# D32_Pro_Breakout_-_TFT_Touch.net
KiCad netlist of a schematic drawn in EAGLE
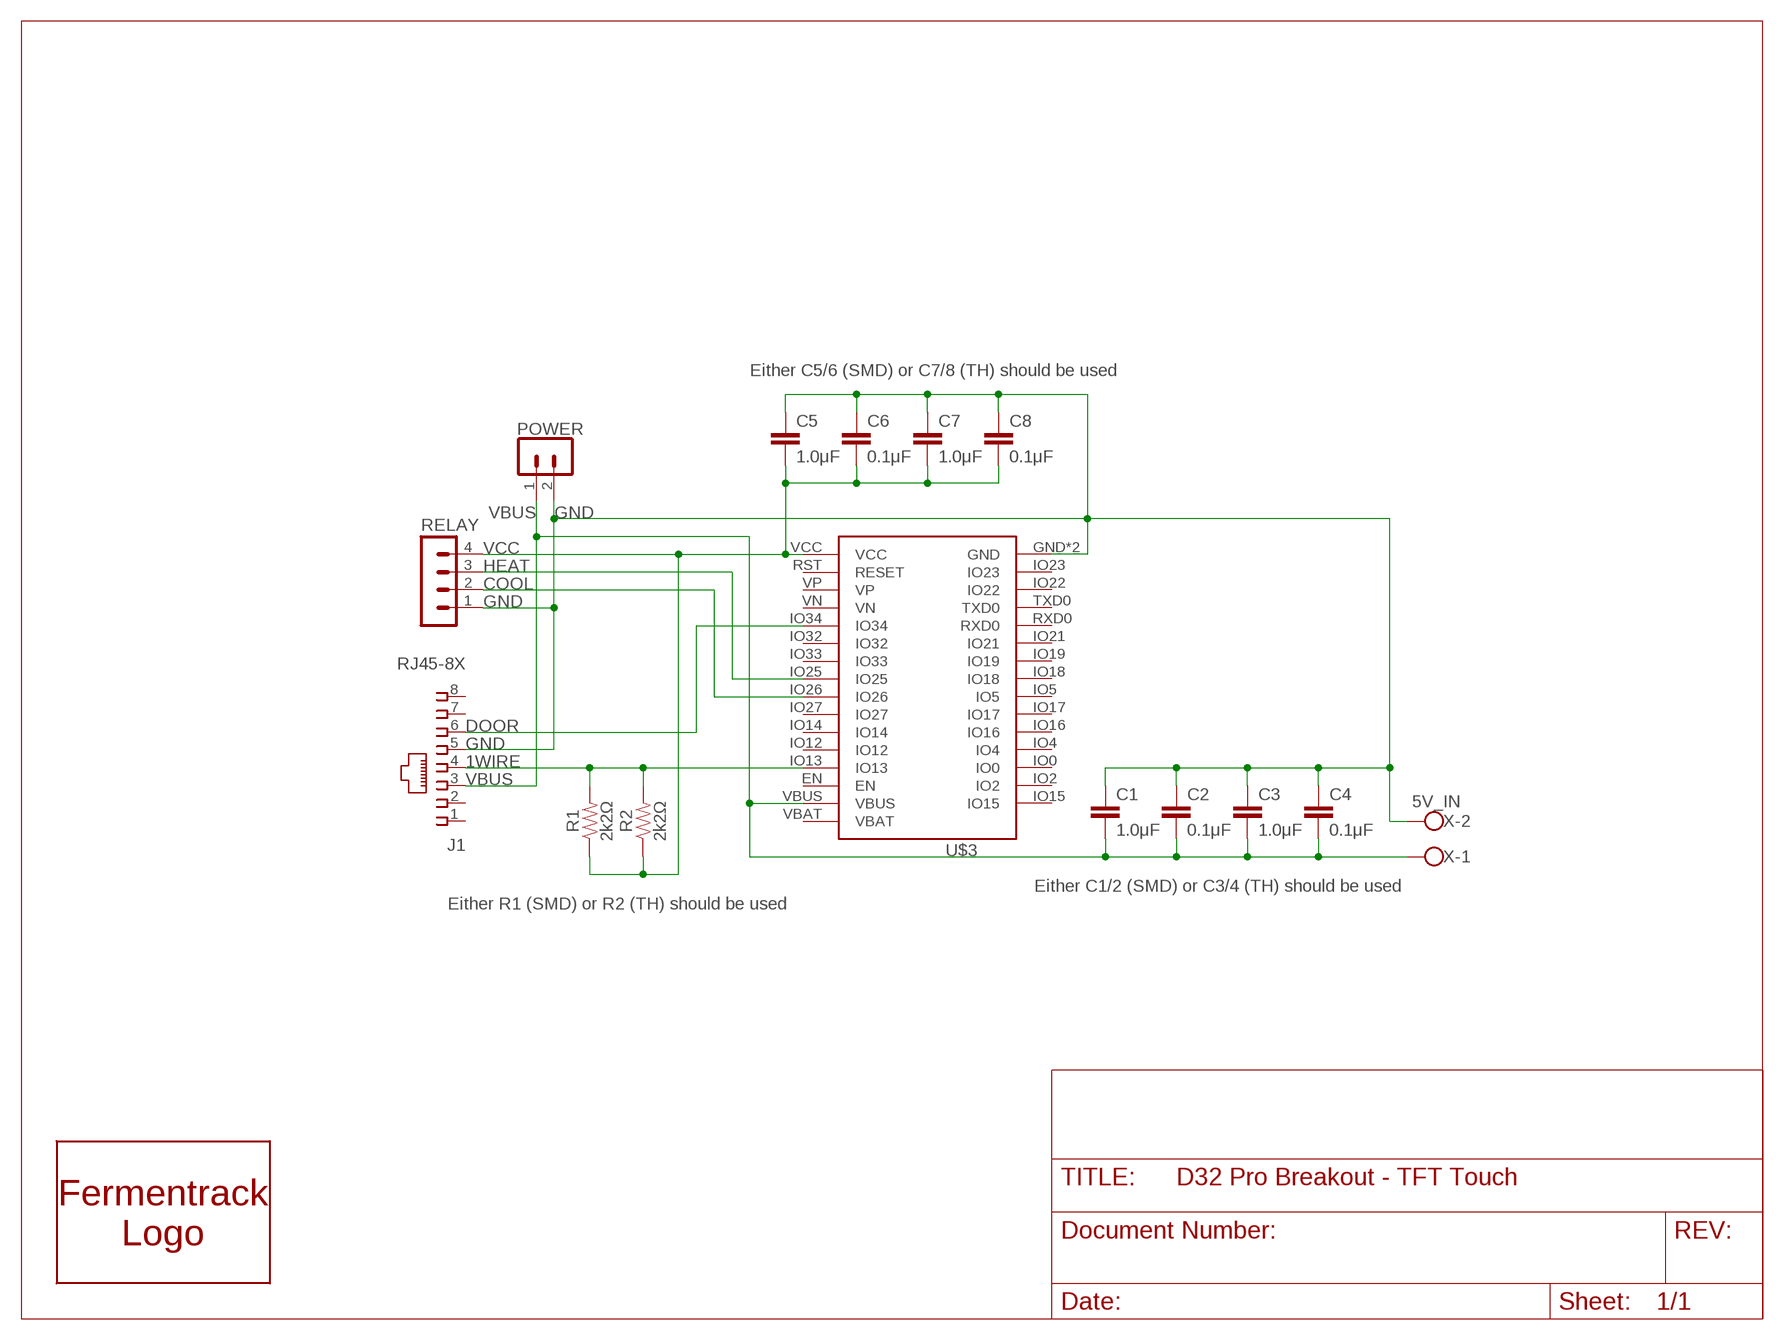
[diagram p0: schematic, sheet 1]

(export (version "E")
  (design (tool "Eeschema 10.0.6"))
  (components
    (comp (ref "C1")
      (value "1.0μF")
      (footprint "eagle-import:SMD-1206")
      (libsource (lib "eagle-import") (part "CAP_SMD1206"))
    )
    (comp (ref "C2")
      (value "0.1μF")
      (footprint "eagle-import:SMD-1206")
      (libsource (lib "eagle-import") (part "CAP_SMD1206"))
    )
    (comp (ref "C3")
      (value "1.0μF")
      (footprint "eagle-import:CAP_PTH-2.54")
      (libsource (lib "eagle-import") (part "CAP_CERAMIC_2.54"))
    )
    (comp (ref "C4")
      (value "0.1μF")
      (footprint "eagle-import:CAP_PTH-2.54")
      (libsource (lib "eagle-import") (part "CAP_CERAMIC_2.54"))
    )
    (comp (ref "C5")
      (value "1.0μF")
      (footprint "eagle-import:SMD-1206")
      (libsource (lib "eagle-import") (part "CAP_SMD1206"))
    )
    (comp (ref "C6")
      (value "0.1μF")
      (footprint "eagle-import:SMD-1206")
      (libsource (lib "eagle-import") (part "CAP_SMD1206"))
    )
    (comp (ref "C7")
      (value "1.0μF")
      (footprint "eagle-import:CAP_PTH-2.54")
      (libsource (lib "eagle-import") (part "CAP_CERAMIC_2.54"))
    )
    (comp (ref "C8")
      (value "0.1μF")
      (footprint "eagle-import:CAP_PTH-2.54")
      (libsource (lib "eagle-import") (part "CAP_CERAMIC_2.54"))
    )
    (comp (ref "J1")
      (value "RJ45-8X")
      (footprint "eagle-import:RJ45-NO-SHIELD-NOLINE")
      (libsource (lib "eagle-import") (part "RJ45-8X"))
    )
    (comp (ref "R1")
      (value "2k2Ω")
      (footprint "eagle-import:SMD-1206")
      (libsource (lib "eagle-import") (part "RES_SMD1206"))
    )
    (comp (ref "R2")
      (value "2k2Ω")
      (footprint "eagle-import:AXIAL-0.3")
      (libsource (lib "eagle-import") (part "1KOHM-HORIZ-1/4W-5%"))
    )
    (comp (ref "RELAY")
      (value "HDR-4")
      (footprint "eagle-import:HDR-4_VERT")
      (libsource (lib "eagle-import") (part "HDR-4"))
    )
    (comp (ref "U$3")
      (value "WEMOS-D32D32_PRO_NO-BATT")
      (footprint "eagle-import:D32_PRO_NO-BATT")
      (libsource (lib "eagle-import") (part "WEMOS-D32D32_PRO_NO-BATT"))
    )
    (comp (ref "U$5")
      (value "POWER")
      (footprint "eagle-import:HDR-2_VERT")
      (libsource (lib "eagle-import") (part "HDR-2"))
    )
    (comp (ref "U$6")
      (value "LOGO_FERMENTRACKFERMENTRACK-LOGO_HALFINCH")
      (footprint "eagle-import:FERMENTRACK-LOGO_SM")
      (libsource (lib "eagle-import") (part "LOGO_FERMENTRACKFERMENTRACK-LOGO_HALFINCH"))
    )
    (comp (ref "X")
      (value "5V_IN")
      (footprint "eagle-import:W237-102")
      (fields (field (name "MPN") "237-102"))
      (libsource (lib "eagle-import") (part "W237-102"))
    )
  )
  (nets
    (net (code "1") (name "/1WIRE") (class "Default")
      (node (ref "J1") (pin "4") (pinfunction "4_4") (pintype "passive"))
      (node (ref "R1") (pin "2") (pinfunction "2_2") (pintype "passive"))
      (node (ref "R2") (pin "P$2") (pinfunction "2_P$2") (pintype "passive"))
      (node (ref "U$3") (pin "IO13") (pinfunction "IO13_IO13") (pintype "bidirectional"))
    )
    (net (code "2") (name "/COOL") (class "Default")
      (node (ref "RELAY") (pin "2") (pinfunction "2_2") (pintype "passive"))
      (node (ref "U$3") (pin "IO26") (pinfunction "IO26_IO26") (pintype "bidirectional"))
    )
    (net (code "3") (name "/DOOR") (class "Default")
      (node (ref "J1") (pin "6") (pinfunction "6_6") (pintype "passive"))
      (node (ref "U$3") (pin "IO34") (pinfunction "IO34_IO34") (pintype "bidirectional"))
    )
    (net (code "4") (name "/GND") (class "Default")
      (node (ref "C1") (pin "1") (pinfunction "1_1") (pintype "passive"))
      (node (ref "C2") (pin "1") (pinfunction "1_1") (pintype "passive"))
      (node (ref "C3") (pin "1") (pinfunction "1_1") (pintype "passive"))
      (node (ref "C4") (pin "1") (pinfunction "1_1") (pintype "passive"))
      (node (ref "C5") (pin "1") (pinfunction "1_1") (pintype "passive"))
      (node (ref "C6") (pin "1") (pinfunction "1_1") (pintype "passive"))
      (node (ref "C7") (pin "1") (pinfunction "1_1") (pintype "passive"))
      (node (ref "C8") (pin "1") (pinfunction "1_1") (pintype "passive"))
      (node (ref "J1") (pin "5") (pinfunction "5_5") (pintype "passive"))
      (node (ref "RELAY") (pin "1") (pinfunction "1_1") (pintype "passive"))
      (node (ref "U$3") (pin "GND") (pinfunction "GND_GND") (pintype "power_in"))
      (node (ref "U$3") (pin "GND2") (pinfunction "GND_GND2") (pintype "power_in"))
      (node (ref "U$5") (pin "2") (pinfunction "2_2") (pintype "passive"))
      (node (ref "X") (pin "2") (pinfunction "KL_2") (pintype "passive"))
    )
    (net (code "5") (name "/HEAT") (class "Default")
      (node (ref "RELAY") (pin "3") (pinfunction "3_3") (pintype "passive"))
      (node (ref "U$3") (pin "IO25") (pinfunction "IO25_IO25") (pintype "bidirectional"))
    )
    (net (code "6") (name "/VBUS") (class "Default")
      (node (ref "C1") (pin "2") (pinfunction "2_2") (pintype "passive"))
      (node (ref "C2") (pin "2") (pinfunction "2_2") (pintype "passive"))
      (node (ref "C3") (pin "2") (pinfunction "2_2") (pintype "passive"))
      (node (ref "C4") (pin "2") (pinfunction "2_2") (pintype "passive"))
      (node (ref "J1") (pin "3") (pinfunction "3_3") (pintype "passive"))
      (node (ref "U$3") (pin "VBUS") (pinfunction "VBUS_VBUS") (pintype "bidirectional"))
      (node (ref "U$5") (pin "1") (pinfunction "1_1") (pintype "passive"))
      (node (ref "X") (pin "1") (pinfunction "KL_1") (pintype "passive"))
    )
    (net (code "7") (name "/VCC") (class "Default")
      (node (ref "C5") (pin "2") (pinfunction "2_2") (pintype "passive"))
      (node (ref "C6") (pin "2") (pinfunction "2_2") (pintype "passive"))
      (node (ref "C7") (pin "2") (pinfunction "2_2") (pintype "passive"))
      (node (ref "C8") (pin "2") (pinfunction "2_2") (pintype "passive"))
      (node (ref "R1") (pin "1") (pinfunction "1_1") (pintype "passive"))
      (node (ref "R2") (pin "P$1") (pinfunction "1_P$1") (pintype "passive"))
      (node (ref "RELAY") (pin "4") (pinfunction "4_4") (pintype "passive"))
      (node (ref "U$3") (pin "VCC") (pinfunction "VCC_VCC") (pintype "power_in"))
    )
    (net (code "8") (name "unconnected-(J1-Pad1)") (class "Default")
      (node (ref "J1") (pin "1") (pinfunction "1_1") (pintype "passive"))
    )
    (net (code "9") (name "unconnected-(J1-Pad2)") (class "Default")
      (node (ref "J1") (pin "2") (pinfunction "2_2") (pintype "passive"))
    )
    (net (code "10") (name "unconnected-(J1-Pad7)") (class "Default")
      (node (ref "J1") (pin "7") (pinfunction "7_7") (pintype "passive"))
    )
    (net (code "11") (name "unconnected-(J1-Pad8)") (class "Default")
      (node (ref "J1") (pin "8") (pinfunction "8_8") (pintype "passive"))
    )
    (net (code "12") (name "unconnected-(U$3-PadEN)") (class "Default")
      (node (ref "U$3") (pin "EN") (pinfunction "EN_EN") (pintype "bidirectional"))
    )
    (net (code "13") (name "unconnected-(U$3-PadIO0)") (class "Default")
      (node (ref "U$3") (pin "IO0") (pinfunction "IO0_IO0") (pintype "bidirectional"))
    )
    (net (code "14") (name "unconnected-(U$3-PadIO2)") (class "Default")
      (node (ref "U$3") (pin "IO2") (pinfunction "IO2_IO2") (pintype "bidirectional"))
    )
    (net (code "15") (name "unconnected-(U$3-PadIO4)") (class "Default")
      (node (ref "U$3") (pin "IO4") (pinfunction "IO4_IO4") (pintype "bidirectional"))
    )
    (net (code "16") (name "unconnected-(U$3-PadIO5)") (class "Default")
      (node (ref "U$3") (pin "IO5") (pinfunction "IO5_IO5") (pintype "bidirectional"))
    )
    (net (code "17") (name "unconnected-(U$3-PadIO12)") (class "Default")
      (node (ref "U$3") (pin "IO12") (pinfunction "IO12_IO12") (pintype "bidirectional"))
    )
    (net (code "18") (name "unconnected-(U$3-PadIO14)") (class "Default")
      (node (ref "U$3") (pin "IO14") (pinfunction "IO14_IO14") (pintype "bidirectional"))
    )
    (net (code "19") (name "unconnected-(U$3-PadIO15)") (class "Default")
      (node (ref "U$3") (pin "IO15") (pinfunction "IO15_IO15") (pintype "bidirectional"))
    )
    (net (code "20") (name "unconnected-(U$3-PadIO16)") (class "Default")
      (node (ref "U$3") (pin "IO16") (pinfunction "IO16_IO16") (pintype "bidirectional"))
    )
    (net (code "21") (name "unconnected-(U$3-PadIO17)") (class "Default")
      (node (ref "U$3") (pin "IO17") (pinfunction "IO17_IO17") (pintype "bidirectional"))
    )
    (net (code "22") (name "unconnected-(U$3-PadIO18)") (class "Default")
      (node (ref "U$3") (pin "IO18") (pinfunction "IO18_IO18") (pintype "bidirectional"))
    )
    (net (code "23") (name "unconnected-(U$3-PadIO19)") (class "Default")
      (node (ref "U$3") (pin "IO19") (pinfunction "IO19_IO19") (pintype "bidirectional"))
    )
    (net (code "24") (name "unconnected-(U$3-PadIO21)") (class "Default")
      (node (ref "U$3") (pin "IO21") (pinfunction "IO21_IO21") (pintype "bidirectional"))
    )
    (net (code "25") (name "unconnected-(U$3-PadIO22)") (class "Default")
      (node (ref "U$3") (pin "IO22") (pinfunction "IO22_IO22") (pintype "bidirectional"))
    )
    (net (code "26") (name "unconnected-(U$3-PadIO23)") (class "Default")
      (node (ref "U$3") (pin "IO23") (pinfunction "IO23_IO23") (pintype "bidirectional"))
    )
    (net (code "27") (name "unconnected-(U$3-PadIO27)") (class "Default")
      (node (ref "U$3") (pin "IO27") (pinfunction "IO27_IO27") (pintype "bidirectional"))
    )
    (net (code "28") (name "unconnected-(U$3-PadIO32)") (class "Default")
      (node (ref "U$3") (pin "IO32") (pinfunction "IO32_IO32") (pintype "bidirectional"))
    )
    (net (code "29") (name "unconnected-(U$3-PadIO33)") (class "Default")
      (node (ref "U$3") (pin "IO33") (pinfunction "IO33_IO33") (pintype "bidirectional"))
    )
    (net (code "30") (name "unconnected-(U$3-PadRXD0)") (class "Default")
      (node (ref "U$3") (pin "RXD0") (pinfunction "RXD0_RXD0") (pintype "input"))
    )
    (net (code "31") (name "unconnected-(U$3-PadTXD0)") (class "Default")
      (node (ref "U$3") (pin "TXD0") (pinfunction "TXD0_TXD0") (pintype "output"))
    )
    (net (code "32") (name "unconnected-(U$3-PadVBAT)") (class "Default")
      (node (ref "U$3") (pin "VBAT") (pinfunction "VBAT_VBAT") (pintype "bidirectional"))
    )
    (net (code "33") (name "unconnected-(U$3-PadVN)") (class "Default")
      (node (ref "U$3") (pin "VN") (pinfunction "VN_VN") (pintype "bidirectional"))
    )
    (net (code "34") (name "unconnected-(U$3-PadVP)") (class "Default")
      (node (ref "U$3") (pin "VP") (pinfunction "VP_VP") (pintype "bidirectional"))
    )
    (net (code "35") (name "unconnected-(U$3-RESET-PadRST)") (class "Default")
      (node (ref "U$3") (pin "RST") (pinfunction "RESET_RST") (pintype "bidirectional"))
    )
  )
)
